# LAMEBOY.net
KiCad netlist of a schematic drawn in EAGLE
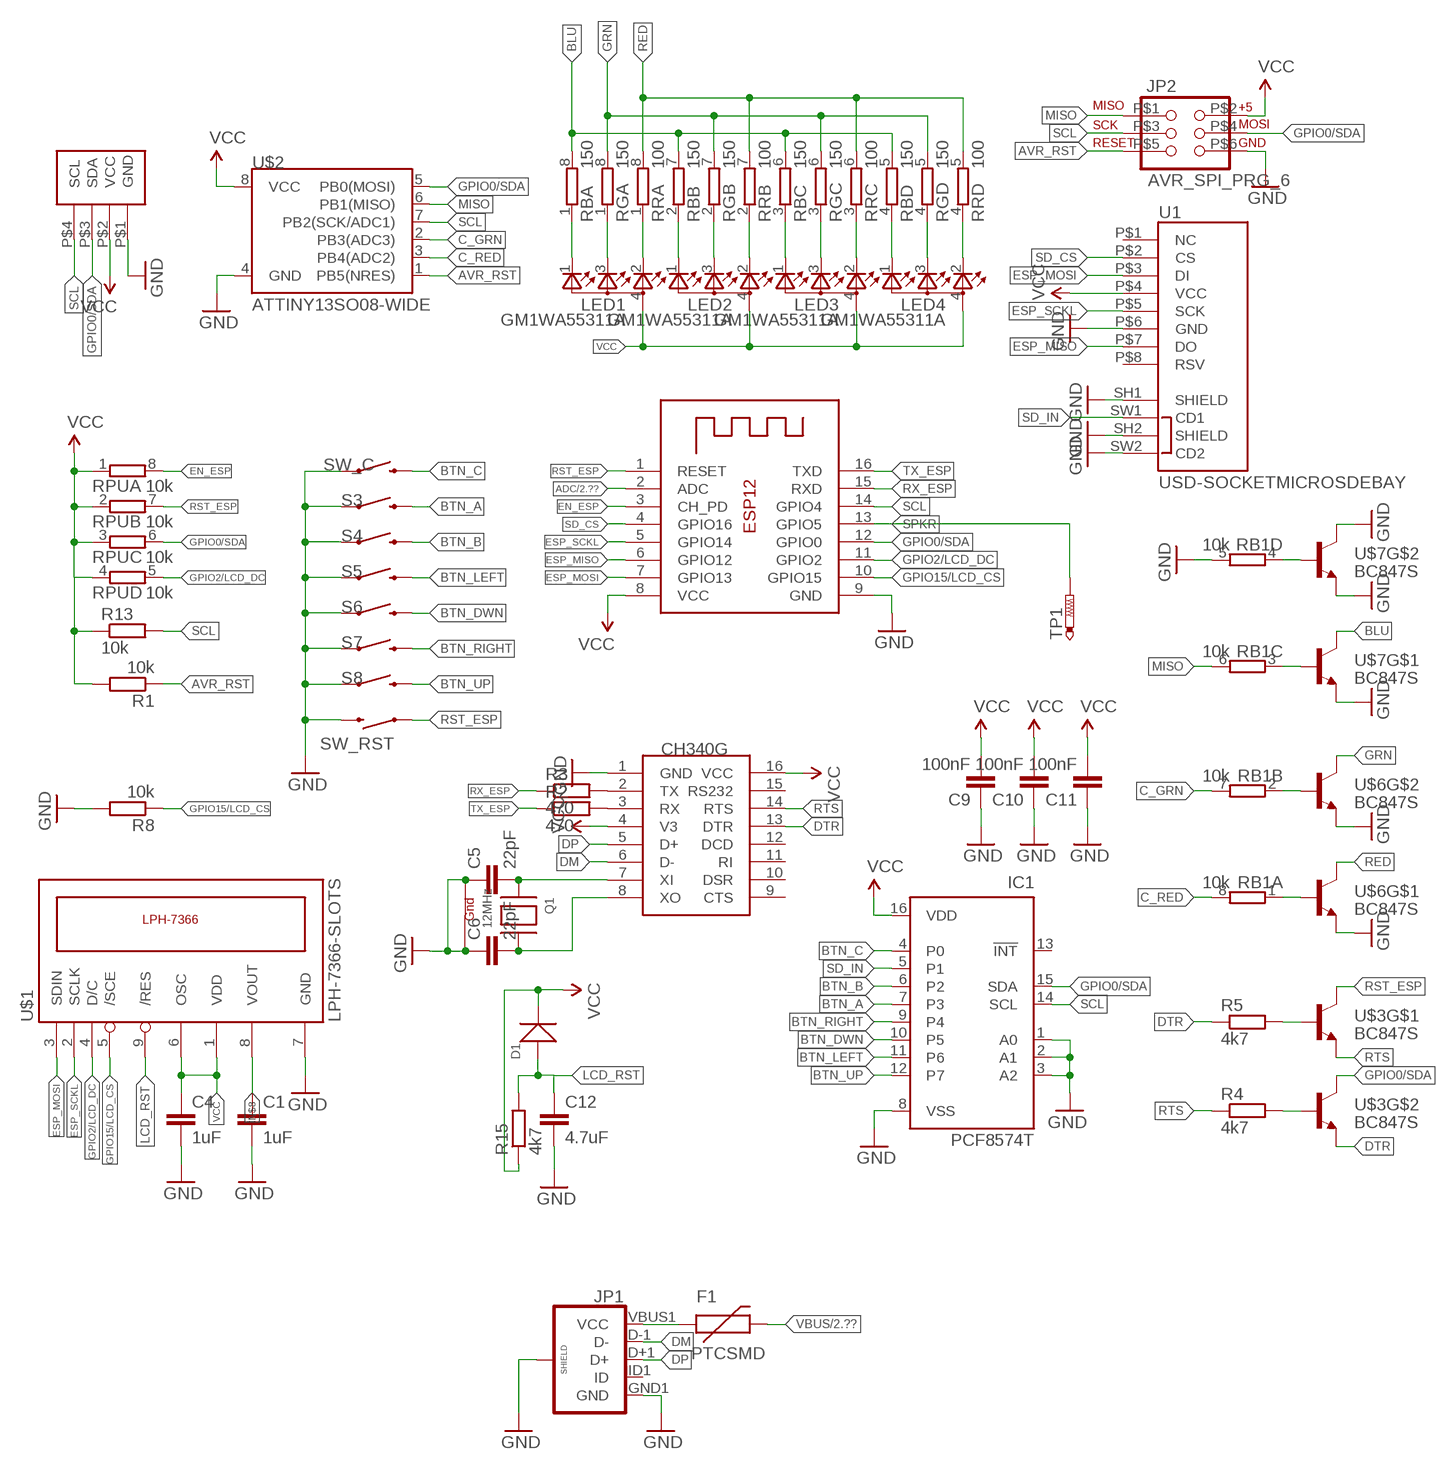
[diagram p0: schematic, sheet 1]
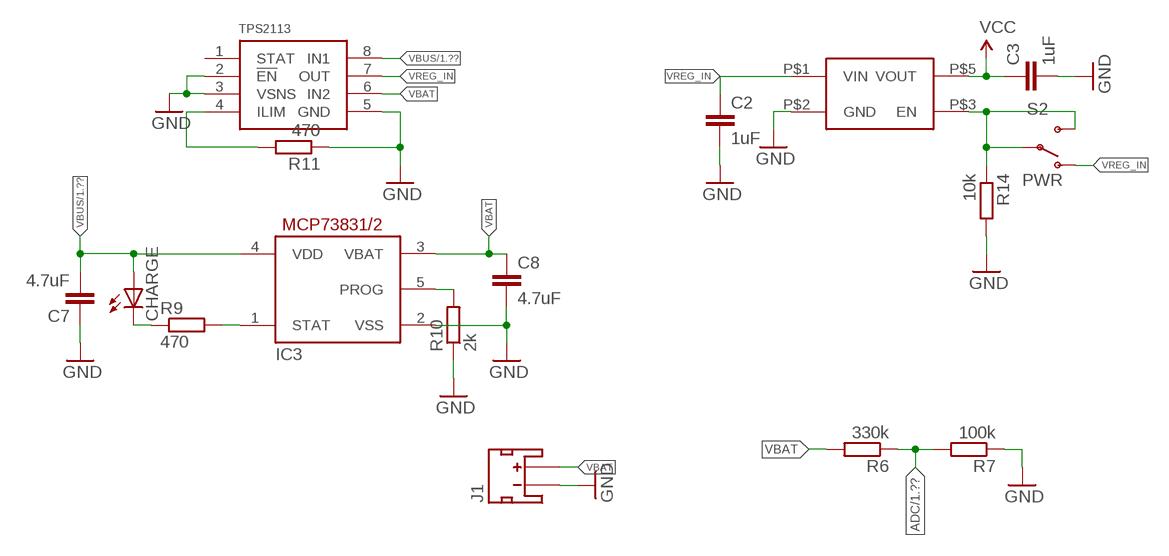
[diagram p1: schematic, sheet 2]

(export (version "E")
  (design (tool "Eeschema 10.0.6"))
  (components
    (comp (ref "C1")
      (value "1uF")
      (footprint "eagle-import:C0805")
      (libsource (lib "eagle-import") (part "C-EUC0805"))
    )
    (comp (ref "C4")
      (value "1uF")
      (footprint "eagle-import:C0805")
      (libsource (lib "eagle-import") (part "C-EUC0805"))
    )
    (comp (ref "C5")
      (value "22pF")
      (footprint "eagle-import:C0805")
      (libsource (lib "eagle-import") (part "C-EUC0805"))
    )
    (comp (ref "C6")
      (value "22pF")
      (footprint "eagle-import:C0805")
      (libsource (lib "eagle-import") (part "C-EUC0805"))
    )
    (comp (ref "C9")
      (value "100nF")
      (footprint "eagle-import:C0805")
      (libsource (lib "eagle-import") (part "C-EUC0805"))
    )
    (comp (ref "C10")
      (value "100nF")
      (footprint "eagle-import:C0805")
      (libsource (lib "eagle-import") (part "C-EUC0805"))
    )
    (comp (ref "C11")
      (value "100nF")
      (footprint "eagle-import:C0805")
      (libsource (lib "eagle-import") (part "C-EUC0805"))
    )
    (comp (ref "C12")
      (value "4.7uF")
      (footprint "eagle-import:C0805")
      (libsource (lib "eagle-import") (part "C-EUC0805"))
    )
    (comp (ref "CH340G")
      (value "CH340GCH340G")
      (footprint "eagle-import:SOIC16")
      (libsource (lib "eagle-import") (part "CH340GCH340G"))
    )
    (comp (ref "D1")
      (value "DIODE'1N4148-SMD'")
      (footprint "eagle-import:LL-34")
      (libsource (lib "eagle-import") (part "DIODE'1N4148-SMD'"))
    )
    (comp (ref "F1")
      (value "PTCSMD")
      (footprint "eagle-import:PTC-1206")
      (libsource (lib "eagle-import") (part "PTCSMD"))
    )
    (comp (ref "IC1")
      (value "PCF8574T")
      (footprint "eagle-import:SO16W")
      (fields (field (name "MPN") "PCF8574T/3,512"))
      (libsource (lib "eagle-import") (part "PCF8574T"))
    )
    (comp (ref "JP1")
      (value "USB_MICROB_PLUG-IDK")
      (footprint "eagle-import:USB-AB-MICRO-SMD_SLOT")
      (libsource (lib "eagle-import") (part "USB_MICROB_PLUG-IDK"))
    )
    (comp (ref "JP2")
      (value "AVR_SPI_PRG_6")
      (footprint "eagle-import:2X3_SMD_PAD")
      (libsource (lib "eagle-import") (part "AVR_SPI_PRG_6"))
    )
    (comp (ref "LED1")
      (value "GM1WA55311A")
      (footprint "eagle-import:GM1WA55311A")
      (libsource (lib "eagle-import") (part "GM1WA55311A"))
    )
    (comp (ref "LED2")
      (value "GM1WA55311A")
      (footprint "eagle-import:GM1WA55311A")
      (libsource (lib "eagle-import") (part "GM1WA55311A"))
    )
    (comp (ref "LED3")
      (value "GM1WA55311A")
      (footprint "eagle-import:GM1WA55311A")
      (libsource (lib "eagle-import") (part "GM1WA55311A"))
    )
    (comp (ref "LED4")
      (value "GM1WA55311A")
      (footprint "eagle-import:GM1WA55311A")
      (libsource (lib "eagle-import") (part "GM1WA55311A"))
    )
    (comp (ref "Q1")
      (value "12MHz")
      (footprint "eagle-import:NX3225_BIGGER")
      (libsource (lib "eagle-import") (part "XTAL-4BIGGER"))
    )
    (comp (ref "R1")
      (value "10k")
      (footprint "eagle-import:R0805")
      (libsource (lib "eagle-import") (part "R-EU_R0805"))
    )
    (comp (ref "R2")
      (value "470")
      (footprint "eagle-import:R0805")
      (libsource (lib "eagle-import") (part "R-EU_R0805"))
    )
    (comp (ref "R3")
      (value "470")
      (footprint "eagle-import:R0805")
      (libsource (lib "eagle-import") (part "R-EU_R0805"))
    )
    (comp (ref "R4")
      (value "4k7")
      (footprint "eagle-import:R0805")
      (libsource (lib "eagle-import") (part "R-EU_R0805"))
    )
    (comp (ref "R5")
      (value "4k7")
      (footprint "eagle-import:R0805")
      (libsource (lib "eagle-import") (part "R-EU_R0805"))
    )
    (comp (ref "R8")
      (value "10k")
      (footprint "eagle-import:R0805")
      (libsource (lib "eagle-import") (part "R-EU_R0805"))
    )
    (comp (ref "R13")
      (value "10k")
      (footprint "eagle-import:R0805")
      (libsource (lib "eagle-import") (part "R-EU_R0805"))
    )
    (comp (ref "R15")
      (value "4k7")
      (footprint "eagle-import:R0805")
      (libsource (lib "eagle-import") (part "R-EU_R0805"))
    )
    (comp (ref "RB")
      (value "150")
      (footprint "eagle-import:0603-ARC")
      (libsource (lib "eagle-import") (part "4R-N0603-ARC"))
    )
    (comp (ref "RB1")
      (value "10k")
      (footprint "eagle-import:0603-ARC")
      (libsource (lib "eagle-import") (part "4R-N0603-ARC"))
    )
    (comp (ref "RG")
      (value "150")
      (footprint "eagle-import:0603-ARC")
      (libsource (lib "eagle-import") (part "4R-N0603-ARC"))
    )
    (comp (ref "RPU")
      (value "10k")
      (footprint "eagle-import:0603-ARC")
      (libsource (lib "eagle-import") (part "4R-N0603-ARC"))
    )
    (comp (ref "RR")
      (value "100")
      (footprint "eagle-import:0603-ARC")
      (libsource (lib "eagle-import") (part "4R-N0603-ARC"))
    )
    (comp (ref "S3")
      (value "SWITCH-MOMENTARY-2SMD-4")
      (footprint "eagle-import:TACTILE_SWITCH_TALL")
      (libsource (lib "eagle-import") (part "SWITCH-MOMENTARY-2SMD-4"))
    )
    (comp (ref "S4")
      (value "SWITCH-MOMENTARY-2SMD-4")
      (footprint "eagle-import:TACTILE_SWITCH_TALL")
      (libsource (lib "eagle-import") (part "SWITCH-MOMENTARY-2SMD-4"))
    )
    (comp (ref "S5")
      (value "SWITCH-MOMENTARY-2SMD-4")
      (footprint "eagle-import:TACTILE_SWITCH_TALL")
      (libsource (lib "eagle-import") (part "SWITCH-MOMENTARY-2SMD-4"))
    )
    (comp (ref "S6")
      (value "SWITCH-MOMENTARY-2SMD-4")
      (footprint "eagle-import:TACTILE_SWITCH_TALL")
      (libsource (lib "eagle-import") (part "SWITCH-MOMENTARY-2SMD-4"))
    )
    (comp (ref "S7")
      (value "SWITCH-MOMENTARY-2SMD-4")
      (footprint "eagle-import:TACTILE_SWITCH_TALL")
      (libsource (lib "eagle-import") (part "SWITCH-MOMENTARY-2SMD-4"))
    )
    (comp (ref "S8")
      (value "SWITCH-MOMENTARY-2SMD-4")
      (footprint "eagle-import:TACTILE_SWITCH_TALL")
      (libsource (lib "eagle-import") (part "SWITCH-MOMENTARY-2SMD-4"))
    )
    (comp (ref "SW_C")
      (value "SWITCH-MOMENTARY-2-SMD-1101NE")
      (footprint "eagle-import:TACTILE-SWITCH-1101NE")
      (libsource (lib "eagle-import") (part "SWITCH-MOMENTARY-2-SMD-1101NE"))
    )
    (comp (ref "SW_RST")
      (value "SWITCH-MOMENTARY-2-SMD-1101NE")
      (footprint "eagle-import:TACTILE-SWITCH-1101NE")
      (libsource (lib "eagle-import") (part "SWITCH-MOMENTARY-2-SMD-1101NE"))
    )
    (comp (ref "TP1")
      (value "PTR1B1,27")
      (footprint "eagle-import:B1,27")
      (libsource (lib "eagle-import") (part "PTR1B1,27"))
    )
    (comp (ref "U$1")
      (value "LPH-7366-SLOTS")
      (footprint "eagle-import:LPH-7366-SLOTS")
      (libsource (lib "eagle-import") (part "LPH-7366-SLOTS"))
    )
    (comp (ref "U$2")
      (value "ATTINY13SO08-WIDE")
      (footprint "eagle-import:SO08-EIAJ")
      (libsource (lib "eagle-import") (part "ATTINY13SO08-WIDE"))
    )
    (comp (ref "U$3")
      (value "BC847S")
      (footprint "eagle-import:SOT363")
      (libsource (lib "eagle-import") (part "MMDT3904"))
    )
    (comp (ref "U$6")
      (value "BC847S")
      (footprint "eagle-import:SOT363")
      (libsource (lib "eagle-import") (part "MMDT3904"))
    )
    (comp (ref "U$7")
      (value "BC847S")
      (footprint "eagle-import:SOT363")
      (libsource (lib "eagle-import") (part "MMDT3904"))
    )
    (comp (ref "U$10")
      (value "I2C_GROVE")
      (footprint "eagle-import:I2C_GROVE")
      (libsource (lib "eagle-import") (part "I2C_GROVE"))
    )
    (comp (ref "U1")
      (value "USD-SOCKETMICROSDEBAY")
      (footprint "eagle-import:MICRO-SD-SOCKET-EBAY")
      (libsource (lib "eagle-import") (part "USD-SOCKETMICROSDEBAY"))
    )
    (comp (ref "X1")
      (value "ESP-12")
      (footprint "eagle-import:ESP-12")
      (libsource (lib "eagle-import") (part "ESP-12"))
    )
    (comp (ref "C2")
      (value "1uF")
      (footprint "eagle-import:C0805")
      (libsource (lib "eagle-import") (part "C-EUC0805"))
    )
    (comp (ref "C3")
      (value "1uF")
      (footprint "eagle-import:C0805")
      (libsource (lib "eagle-import") (part "C-EUC0805"))
    )
    (comp (ref "C7")
      (value "4.7uF")
      (footprint "eagle-import:C0805")
      (libsource (lib "eagle-import") (part "C-EUC0805"))
    )
    (comp (ref "C8")
      (value "4.7uF")
      (footprint "eagle-import:C0805")
      (libsource (lib "eagle-import") (part "C-EUC0805"))
    )
    (comp (ref "CHARGE")
      (value "LEDCHARLIE")
      (footprint "eagle-import:CHIPLED_0603_CHARLIE")
      (libsource (lib "eagle-import") (part "LEDCHARLIE"))
    )
    (comp (ref "IC3")
      (value "MCP73831")
      (footprint "eagle-import:SOT23-5L")
      (libsource (lib "eagle-import") (part "MCP73831/OT"))
    )
    (comp (ref "J1")
      (value "JST_2MM_MALE")
      (footprint "eagle-import:JST-2-SMD")
      (libsource (lib "eagle-import") (part "JST_2MM_MALE"))
    )
    (comp (ref "R6")
      (value "330k")
      (footprint "eagle-import:R0805")
      (libsource (lib "eagle-import") (part "R-EU_R0805"))
    )
    (comp (ref "R7")
      (value "100k")
      (footprint "eagle-import:R0805")
      (libsource (lib "eagle-import") (part "R-EU_R0805"))
    )
    (comp (ref "R9")
      (value "470")
      (footprint "eagle-import:R0805")
      (libsource (lib "eagle-import") (part "R-EU_R0805"))
    )
    (comp (ref "R10")
      (value "2k")
      (footprint "eagle-import:R0805")
      (libsource (lib "eagle-import") (part "R-EU_R0805"))
    )
    (comp (ref "R11")
      (value "470")
      (footprint "eagle-import:R0805")
      (libsource (lib "eagle-import") (part "R-EU_R0805"))
    )
    (comp (ref "R14")
      (value "10k")
      (footprint "eagle-import:R0805")
      (libsource (lib "eagle-import") (part "R-EU_R0805"))
    )
    (comp (ref "S2")
      (value "PWR")
      (footprint "eagle-import:SWITCH-SPST-SMD-A")
      (libsource (lib "eagle-import") (part "SWITCH-SPDT-SMD-A"))
    )
    (comp (ref "U$4")
      (value "TPS2113-PW")
      (footprint "eagle-import:TEXAS-PW")
      (libsource (lib "eagle-import") (part "TPS2113-PW"))
    )
    (comp (ref "U$9")
      (value "AP2112KAP2112K")
      (footprint "eagle-import:AP2112")
      (libsource (lib "eagle-import") (part "AP2112KAP2112K"))
    )
  )
  (nets
    (net (code "1") (name "ADC") (class "Default")
      (node (ref "R6") (pin "1") (pinfunction "1_1") (pintype "passive"))
      (node (ref "R7") (pin "2") (pinfunction "2_2") (pintype "passive"))
      (node (ref "X1") (pin "2") (pinfunction "ADC_2") (pintype "passive"))
    )
    (net (code "2") (name "AVR_RST") (class "Default")
      (node (ref "JP2") (pin "P$5") (pinfunction "5_P$5") (pintype "passive"))
      (node (ref "R1") (pin "1") (pinfunction "1_1") (pintype "passive"))
      (node (ref "U$2") (pin "1") (pinfunction "PB5(NRES)_1") (pintype "bidirectional"))
    )
    (net (code "3") (name "BLU") (class "Default")
      (node (ref "RB") (pin "5") (pinfunction "2_5") (pintype "passive"))
      (node (ref "RB") (pin "6") (pinfunction "2_6") (pintype "passive"))
      (node (ref "RB") (pin "7") (pinfunction "2_7") (pintype "passive"))
      (node (ref "RB") (pin "8") (pinfunction "2_8") (pintype "passive"))
      (node (ref "U$7") (pin "3") (pinfunction "C_3") (pintype "passive"))
    )
    (net (code "4") (name "BTN_A") (class "Default")
      (node (ref "IC1") (pin "7") (pinfunction "P3_7") (pintype "bidirectional"))
      (node (ref "S3") (pin "B2") (pinfunction "2_B2") (pintype "passive"))
    )
    (net (code "5") (name "BTN_B") (class "Default")
      (node (ref "IC1") (pin "6") (pinfunction "P2_6") (pintype "bidirectional"))
      (node (ref "S4") (pin "B2") (pinfunction "2_B2") (pintype "passive"))
    )
    (net (code "6") (name "BTN_C") (class "Default")
      (node (ref "IC1") (pin "4") (pinfunction "P0_4") (pintype "bidirectional"))
      (node (ref "SW_C") (pin "P$2") (pinfunction "2_P$2") (pintype "passive"))
    )
    (net (code "7") (name "BTN_DWN") (class "Default")
      (node (ref "IC1") (pin "10") (pinfunction "P5_10") (pintype "bidirectional"))
      (node (ref "S6") (pin "B2") (pinfunction "2_B2") (pintype "passive"))
    )
    (net (code "8") (name "BTN_LEFT") (class "Default")
      (node (ref "IC1") (pin "11") (pinfunction "P6_11") (pintype "bidirectional"))
      (node (ref "S5") (pin "B2") (pinfunction "2_B2") (pintype "passive"))
    )
    (net (code "9") (name "BTN_RIGHT") (class "Default")
      (node (ref "IC1") (pin "9") (pinfunction "P4_9") (pintype "bidirectional"))
      (node (ref "S7") (pin "B2") (pinfunction "2_B2") (pintype "passive"))
    )
    (net (code "10") (name "BTN_UP") (class "Default")
      (node (ref "IC1") (pin "12") (pinfunction "P7_12") (pintype "bidirectional"))
      (node (ref "S8") (pin "B2") (pinfunction "2_B2") (pintype "passive"))
    )
    (net (code "11") (name "C_GRN") (class "Default")
      (node (ref "RB1") (pin "7") (pinfunction "2_7") (pintype "passive"))
      (node (ref "U$2") (pin "2") (pinfunction "PB3(ADC3)_2") (pintype "bidirectional"))
    )
    (net (code "12") (name "C_RED") (class "Default")
      (node (ref "RB1") (pin "8") (pinfunction "2_8") (pintype "passive"))
      (node (ref "U$2") (pin "3") (pinfunction "PB4(ADC2)_3") (pintype "bidirectional"))
    )
    (net (code "13") (name "DM") (class "Default")
      (node (ref "CH340G") (pin "6") (pinfunction "D-_6") (pintype "bidirectional"))
      (node (ref "JP1") (pin "D-1") (pinfunction "D-_D-1") (pintype "bidirectional"))
    )
    (net (code "14") (name "DP") (class "Default")
      (node (ref "CH340G") (pin "5") (pinfunction "D+_5") (pintype "bidirectional"))
      (node (ref "JP1") (pin "D+1") (pinfunction "D+_D+1") (pintype "bidirectional"))
    )
    (net (code "15") (name "DTR") (class "Default")
      (node (ref "CH340G") (pin "13") (pinfunction "DTR_13") (pintype "bidirectional"))
      (node (ref "R5") (pin "1") (pinfunction "1_1") (pintype "passive"))
      (node (ref "U$3") (pin "1") (pinfunction "E_1") (pintype "passive"))
    )
    (net (code "16") (name "EN_ESP") (class "Default")
      (node (ref "RPU") (pin "8") (pinfunction "2_8") (pintype "passive"))
      (node (ref "X1") (pin "3") (pinfunction "CH_PD_3") (pintype "input"))
    )
    (net (code "17") (name "ESP_MISO") (class "Default")
      (node (ref "U1") (pin "P$7") (pinfunction "DO_P$7") (pintype "bidirectional"))
      (node (ref "X1") (pin "6") (pinfunction "GPIO12_6") (pintype "bidirectional"))
    )
    (net (code "18") (name "ESP_MOSI") (class "Default")
      (node (ref "U$1") (pin "3") (pinfunction "SDIN_3") (pintype "input"))
      (node (ref "U1") (pin "P$3") (pinfunction "DI_P$3") (pintype "bidirectional"))
      (node (ref "X1") (pin "7") (pinfunction "GPIO13_7") (pintype "bidirectional"))
    )
    (net (code "19") (name "ESP_SCKL") (class "Default")
      (node (ref "U$1") (pin "2") (pinfunction "SCLK_2") (pintype "input"))
      (node (ref "U1") (pin "P$5") (pinfunction "SCK_P$5") (pintype "bidirectional"))
      (node (ref "X1") (pin "5") (pinfunction "GPIO14_5") (pintype "bidirectional"))
    )
    (net (code "20") (name "GND") (class "Default")
      (node (ref "C1") (pin "2") (pinfunction "2_2") (pintype "passive"))
      (node (ref "C10") (pin "1") (pinfunction "1_1") (pintype "passive"))
      (node (ref "C11") (pin "1") (pinfunction "1_1") (pintype "passive"))
      (node (ref "C12") (pin "2") (pinfunction "2_2") (pintype "passive"))
      (node (ref "C2") (pin "2") (pinfunction "2_2") (pintype "passive"))
      (node (ref "C3") (pin "2") (pinfunction "2_2") (pintype "passive"))
      (node (ref "C4") (pin "2") (pinfunction "2_2") (pintype "passive"))
      (node (ref "C5") (pin "1") (pinfunction "1_1") (pintype "passive"))
      (node (ref "C6") (pin "1") (pinfunction "1_1") (pintype "passive"))
      (node (ref "C7") (pin "1") (pinfunction "1_1") (pintype "passive"))
      (node (ref "C8") (pin "2") (pinfunction "2_2") (pintype "passive"))
      (node (ref "C9") (pin "1") (pinfunction "1_1") (pintype "passive"))
      (node (ref "CH340G") (pin "1") (pinfunction "GND_1") (pintype "bidirectional"))
      (node (ref "IC1") (pin "1") (pinfunction "A0_1") (pintype "input"))
      (node (ref "IC1") (pin "2") (pinfunction "A1_2") (pintype "input"))
      (node (ref "IC1") (pin "3") (pinfunction "A2_3") (pintype "input"))
      (node (ref "IC1") (pin "8") (pinfunction "VSS_8") (pintype "power_in"))
      (node (ref "IC3") (pin "2") (pinfunction "VSS_2") (pintype "power_in"))
      (node (ref "J1") (pin "1") (pinfunction "-_1") (pintype "bidirectional"))
      (node (ref "JP1") (pin "GND1") (pinfunction "GND_GND1") (pintype "bidirectional"))
      (node (ref "JP1") (pin "P$1") (pinfunction "SHIELD_P$1") (pintype "bidirectional"))
      (node (ref "JP1") (pin "P$2") (pinfunction "SHIELD_P$2") (pintype "bidirectional"))
      (node (ref "JP1") (pin "P$3") (pinfunction "SHIELD_P$3") (pintype "bidirectional"))
      (node (ref "JP1") (pin "P$4") (pinfunction "SHIELD_P$4") (pintype "bidirectional"))
      (node (ref "JP2") (pin "P$6") (pinfunction "6_P$6") (pintype "passive"))
      (node (ref "Q1") (pin "2") (pinfunction "G2_2") (pintype "power_in"))
      (node (ref "Q1") (pin "4") (pinfunction "G1_4") (pintype "power_in"))
      (node (ref "R10") (pin "1") (pinfunction "1_1") (pintype "passive"))
      (node (ref "R11") (pin "1") (pinfunction "1_1") (pintype "passive"))
      (node (ref "R14") (pin "2") (pinfunction "2_2") (pintype "passive"))
      (node (ref "R7") (pin "1") (pinfunction "1_1") (pintype "passive"))
      (node (ref "R8") (pin "2") (pinfunction "2_2") (pintype "passive"))
      (node (ref "RB1") (pin "5") (pinfunction "2_5") (pintype "passive"))
      (node (ref "S3") (pin "A2") (pinfunction "1_A2") (pintype "passive"))
      (node (ref "S4") (pin "A2") (pinfunction "1_A2") (pintype "passive"))
      (node (ref "S5") (pin "A2") (pinfunction "1_A2") (pintype "passive"))
      (node (ref "S6") (pin "A2") (pinfunction "1_A2") (pintype "passive"))
      (node (ref "S7") (pin "A2") (pinfunction "1_A2") (pintype "passive"))
      (node (ref "S8") (pin "A2") (pinfunction "1_A2") (pintype "passive"))
      (node (ref "SW_C") (pin "P$1") (pinfunction "1_P$1") (pintype "passive"))
      (node (ref "SW_RST") (pin "P$2") (pinfunction "2_P$2") (pintype "passive"))
      (node (ref "U$1") (pin "7") (pinfunction "GND_7") (pintype "power_in"))
      (node (ref "U$10") (pin "P$1") (pinfunction "GND_P$1") (pintype "bidirectional"))
      (node (ref "U$2") (pin "4") (pinfunction "GND_4") (pintype "bidirectional"))
      (node (ref "U$4") (pin "2") (pinfunction "~{EN}_2") (pintype "bidirectional"))
      (node (ref "U$4") (pin "3") (pinfunction "VSNS_3") (pintype "bidirectional"))
      (node (ref "U$4") (pin "5") (pinfunction "GND_5") (pintype "bidirectional"))
      (node (ref "U$6") (pin "1") (pinfunction "E_1") (pintype "passive"))
      (node (ref "U$6") (pin "4") (pinfunction "E_4") (pintype "passive"))
      (node (ref "U$7") (pin "1") (pinfunction "E_1") (pintype "passive"))
      (node (ref "U$7") (pin "4") (pinfunction "E_4") (pintype "passive"))
      (node (ref "U$7") (pin "6") (pinfunction "C_6") (pintype "passive"))
      (node (ref "U$9") (pin "P$2") (pinfunction "GND_P$2") (pintype "bidirectional"))
      (node (ref "U1") (pin "P$6") (pinfunction "GND_P$6") (pintype "bidirectional"))
      (node (ref "U1") (pin "SH1") (pinfunction "SHIELD_SH1") (pintype "bidirectional"))
      (node (ref "U1") (pin "SH2") (pinfunction "SHIELD_SH2") (pintype "bidirectional"))
      (node (ref "U1") (pin "SW2") (pinfunction "CD2_SW2") (pintype "bidirectional"))
      (node (ref "X1") (pin "9") (pinfunction "GND_9") (pintype "power_in"))
    )
    (net (code "21") (name "GPIO0{slash}SDA") (class "Default")
      (node (ref "IC1") (pin "15") (pinfunction "SDA_15") (pintype "bidirectional"))
      (node (ref "JP2") (pin "P$4") (pinfunction "4_P$4") (pintype "passive"))
      (node (ref "RPU") (pin "6") (pinfunction "2_6") (pintype "passive"))
      (node (ref "U$10") (pin "P$3") (pinfunction "SDA_P$3") (pintype "bidirectional"))
      (node (ref "U$2") (pin "5") (pinfunction "PB0(MOSI)_5") (pintype "bidirectional"))
      (node (ref "U$3") (pin "6") (pinfunction "C_6") (pintype "passive"))
      (node (ref "X1") (pin "12") (pinfunction "GPIO0_12") (pintype "bidirectional"))
    )
    (net (code "22") (name "GPIO2{slash}LCD_DC") (class "Default")
      (node (ref "RPU") (pin "5") (pinfunction "2_5") (pintype "passive"))
      (node (ref "U$1") (pin "4") (pinfunction "D/C_4") (pintype "input"))
      (node (ref "X1") (pin "11") (pinfunction "GPIO2_11") (pintype "bidirectional"))
    )
    (net (code "23") (name "GPIO15{slash}LCD_CS") (class "Default")
      (node (ref "R8") (pin "1") (pinfunction "1_1") (pintype "passive"))
      (node (ref "U$1") (pin "5") (pinfunction "/SCE_5") (pintype "input"))
      (node (ref "X1") (pin "10") (pinfunction "GPIO15_10") (pintype "bidirectional"))
    )
    (net (code "24") (name "GRN") (class "Default")
      (node (ref "RG") (pin "5") (pinfunction "2_5") (pintype "passive"))
      (node (ref "RG") (pin "6") (pinfunction "2_6") (pintype "passive"))
      (node (ref "RG") (pin "7") (pinfunction "2_7") (pintype "passive"))
      (node (ref "RG") (pin "8") (pinfunction "2_8") (pintype "passive"))
      (node (ref "U$6") (pin "6") (pinfunction "C_6") (pintype "passive"))
    )
    (net (code "25") (name "LCD_RST") (class "Default")
      (node (ref "C12") (pin "1") (pinfunction "1_1") (pintype "passive"))
      (node (ref "D1") (pin "A") (pinfunction "+_A") (pintype "passive"))
      (node (ref "R15") (pin "2") (pinfunction "2_2") (pintype "passive"))
      (node (ref "U$1") (pin "9") (pinfunction "/RES_9") (pintype "input"))
    )
    (net (code "26") (name "MISO") (class "Default")
      (node (ref "JP2") (pin "P$1") (pinfunction "1_P$1") (pintype "passive"))
      (node (ref "RB1") (pin "6") (pinfunction "2_6") (pintype "passive"))
      (node (ref "U$2") (pin "6") (pinfunction "PB1(MISO)_6") (pintype "bidirectional"))
    )
    (net (code "27") (name "N$8") (class "Default")
      (node (ref "C1") (pin "1") (pinfunction "1_1") (pintype "passive"))
      (node (ref "U$1") (pin "8") (pinfunction "VOUT_8") (pintype "passive"))
    )
    (net (code "28") (name "Net-(CH340G-RX)") (class "Default")
      (node (ref "CH340G") (pin "3") (pinfunction "RX_3") (pintype "bidirectional"))
      (node (ref "R2") (pin "2") (pinfunction "2_2") (pintype "passive"))
    )
    (net (code "29") (name "Net-(CH340G-TX)") (class "Default")
      (node (ref "CH340G") (pin "2") (pinfunction "TX_2") (pintype "bidirectional"))
      (node (ref "R3") (pin "2") (pinfunction "2_2") (pintype "passive"))
    )
    (net (code "30") (name "Net-(CH340G-XI)") (class "Default")
      (node (ref "C5") (pin "2") (pinfunction "2_2") (pintype "passive"))
      (node (ref "CH340G") (pin "7") (pinfunction "XI_7") (pintype "bidirectional"))
      (node (ref "Q1") (pin "1") (pinfunction "X1_1") (pintype "bidirectional"))
    )
    (net (code "31") (name "Net-(CH340G-XO)") (class "Default")
      (node (ref "C6") (pin "2") (pinfunction "2_2") (pintype "passive"))
      (node (ref "CH340G") (pin "8") (pinfunction "XO_8") (pintype "bidirectional"))
      (node (ref "Q1") (pin "3") (pinfunction "X2_3") (pintype "bidirectional"))
    )
    (net (code "32") (name "Net-(CHARGE-PadC)") (class "Default")
      (node (ref "CHARGE") (pin "C") (pinfunction "C_C") (pintype "passive"))
      (node (ref "R9") (pin "1") (pinfunction "1_1") (pintype "passive"))
    )
    (net (code "33") (name "Net-(IC3-PROG)") (class "Default")
      (node (ref "IC3") (pin "5") (pinfunction "PROG_5") (pintype "input"))
      (node (ref "R10") (pin "2") (pinfunction "2_2") (pintype "passive"))
    )
    (net (code "34") (name "Net-(IC3-STAT)") (class "Default")
      (node (ref "IC3") (pin "1") (pinfunction "STAT_1") (pintype "output"))
      (node (ref "R9") (pin "2") (pinfunction "2_2") (pintype "passive"))
    )
    (net (code "35") (name "Net-(JP1-VCC)") (class "Default")
      (node (ref "F1") (pin "1") (pinfunction "1_1") (pintype "bidirectional"))
      (node (ref "JP1") (pin "VBUS1") (pinfunction "VCC_VBUS1") (pintype "bidirectional"))
    )
    (net (code "36") (name "Net-(LED1-CBLUE)") (class "Default")
      (node (ref "LED1") (pin "3") (pinfunction "CBLUE_3") (pintype "passive"))
      (node (ref "RG") (pin "1") (pinfunction "1_1") (pintype "passive"))
    )
    (net (code "37") (name "Net-(LED1-CGREEN)") (class "Default")
      (node (ref "LED1") (pin "1") (pinfunction "CGREEN_1") (pintype "passive"))
      (node (ref "RB") (pin "1") (pinfunction "1_1") (pintype "passive"))
    )
    (net (code "38") (name "Net-(LED1-CRED)") (class "Default")
      (node (ref "LED1") (pin "2") (pinfunction "CRED_2") (pintype "passive"))
      (node (ref "RR") (pin "1") (pinfunction "1_1") (pintype "passive"))
    )
    (net (code "39") (name "Net-(LED2-CBLUE)") (class "Default")
      (node (ref "LED2") (pin "3") (pinfunction "CBLUE_3") (pintype "passive"))
      (node (ref "RG") (pin "2") (pinfunction "1_2") (pintype "passive"))
    )
    (net (code "40") (name "Net-(LED2-CGREEN)") (class "Default")
      (node (ref "LED2") (pin "1") (pinfunction "CGREEN_1") (pintype "passive"))
      (node (ref "RB") (pin "2") (pinfunction "1_2") (pintype "passive"))
    )
    (net (code "41") (name "Net-(LED2-CRED)") (class "Default")
      (node (ref "LED2") (pin "2") (pinfunction "CRED_2") (pintype "passive"))
      (node (ref "RR") (pin "2") (pinfunction "1_2") (pintype "passive"))
    )
    (net (code "42") (name "Net-(LED3-CBLUE)") (class "Default")
      (node (ref "LED3") (pin "3") (pinfunction "CBLUE_3") (pintype "passive"))
      (node (ref "RG") (pin "3") (pinfunction "1_3") (pintype "passive"))
    )
    (net (code "43") (name "Net-(LED3-CGREEN)") (class "Default")
      (node (ref "LED3") (pin "1") (pinfunction "CGREEN_1") (pintype "passive"))
      (node (ref "RB") (pin "3") (pinfunction "1_3") (pintype "passive"))
    )
    (net (code "44") (name "Net-(LED3-CRED)") (class "Default")
      (node (ref "LED3") (pin "2") (pinfunction "CRED_2") (pintype "passive"))
      (node (ref "RR") (pin "3") (pinfunction "1_3") (pintype "passive"))
    )
    (net (code "45") (name "Net-(LED4-CBLUE)") (class "Default")
      (node (ref "LED4") (pin "3") (pinfunction "CBLUE_3") (pintype "passive"))
      (node (ref "RG") (pin "4") (pinfunction "1_4") (pintype "passive"))
    )
    (net (code "46") (name "Net-(LED4-CGREEN)") (class "Default")
      (node (ref "LED4") (pin "1") (pinfunction "CGREEN_1") (pintype "passive"))
      (node (ref "RB") (pin "4") (pinfunction "1_4") (pintype "passive"))
    )
    (net (code "47") (name "Net-(LED4-CRED)") (class "Default")
      (node (ref "LED4") (pin "2") (pinfunction "CRED_2") (pintype "passive"))
      (node (ref "RR") (pin "4") (pinfunction "1_4") (pintype "passive"))
    )
    (net (code "48") (name "Net-(RB1B-1)") (class "Default")
      (node (ref "RB1") (pin "2") (pinfunction "1_2") (pintype "passive"))
      (node (ref "U$6") (pin "2") (pinfunction "B_2") (pintype "passive"))
    )
    (net (code "49") (name "Net-(RB1C-1)") (class "Default")
      (node (ref "RB1") (pin "3") (pinfunction "1_3") (pintype "passive"))
      (node (ref "U$7") (pin "5") (pinfunction "B_5") (pintype "passive"))
    )
    (net (code "50") (name "Net-(RB1D-1)") (class "Default")
      (node (ref "RB1") (pin "4") (pinfunction "1_4") (pintype "passive"))
      (node (ref "U$7") (pin "2") (pinfunction "B_2") (pintype "passive"))
    )
    (net (code "51") (name "Net-(S2-P)") (class "Default")
      (node (ref "R14") (pin "1") (pinfunction "1_1") (pintype "passive"))
      (node (ref "S2") (pin "2") (pinfunction "P_2") (pintype "passive"))
      (node (ref "S2") (pin "3") (pinfunction "S_3") (pintype "passive"))
      (node (ref "U$9") (pin "P$3") (pinfunction "EN_P$3") (pintype "bidirectional"))
    )
    (net (code "52") (name "Net-(U$3A-B)") (class "Default")
      (node (ref "R5") (pin "2") (pinfunction "2_2") (pintype "passive"))
      (node (ref "U$3") (pin "5") (pinfunction "B_5") (pintype "passive"))
    )
    (net (code "53") (name "Net-(U$3B-B)") (class "Default")
      (node (ref "R4") (pin "2") (pinfunction "2_2") (pintype "passive"))
      (node (ref "U$3") (pin "2") (pinfunction "B_2") (pintype "passive"))
    )
    (net (code "54") (name "Net-(U$4-ILIM)") (class "Default")
      (node (ref "R11") (pin "2") (pinfunction "2_2") (pintype "passive"))
      (node (ref "U$4") (pin "4") (pinfunction "ILIM_4") (pintype "bidirectional"))
    )
    (net (code "55") (name "Net-(U$6A-B)") (class "Default")
      (node (ref "RB1") (pin "1") (pinfunction "1_1") (pintype "passive"))
      (node (ref "U$6") (pin "5") (pinfunction "B_5") (pintype "passive"))
    )
    (net (code "56") (name "RED") (class "Default")
      (node (ref "RR") (pin "5") (pinfunction "2_5") (pintype "passive"))
      (node (ref "RR") (pin "6") (pinfunction "2_6") (pintype "passive"))
      (node (ref "RR") (pin "7") (pinfunction "2_7") (pintype "passive"))
      (node (ref "RR") (pin "8") (pinfunction "2_8") (pintype "passive"))
      (node (ref "U$6") (pin "3") (pinfunction "C_3") (pintype "passive"))
    )
    (net (code "57") (name "RST_ESP") (class "Default")
      (node (ref "RPU") (pin "7") (pinfunction "2_7") (pintype "passive"))
      (node (ref "SW_RST") (pin "P$1") (pinfunction "1_P$1") (pintype "passive"))
      (node (ref "U$3") (pin "3") (pinfunction "C_3") (pintype "passive"))
      (node (ref "X1") (pin "1") (pinfunction "RESET_1") (pintype "input"))
    )
    (net (code "58") (name "RTS") (class "Default")
      (node (ref "CH340G") (pin "14") (pinfunction "RTS_14") (pintype "bidirectional"))
      (node (ref "R4") (pin "1") (pinfunction "1_1") (pintype "passive"))
      (node (ref "U$3") (pin "4") (pinfunction "E_4") (pintype "passive"))
    )
    (net (code "59") (name "RX_ESP") (class "Default")
      (node (ref "R3") (pin "1") (pinfunction "1_1") (pintype "passive"))
      (node (ref "X1") (pin "15") (pinfunction "RXD_15") (pintype "input"))
    )
    (net (code "60") (name "SCL") (class "Default")
      (node (ref "IC1") (pin "14") (pinfunction "SCL_14") (pintype "input"))
      (node (ref "JP2") (pin "P$3") (pinfunction "3_P$3") (pintype "passive"))
      (node (ref "R13") (pin "2") (pinfunction "2_2") (pintype "passive"))
      (node (ref "U$10") (pin "P$4") (pinfunction "SCL_P$4") (pintype "bidirectional"))
      (node (ref "U$2") (pin "7") (pinfunction "PB2(SCK/ADC1)_7") (pintype "bidirectional"))
      (node (ref "X1") (pin "14") (pinfunction "GPIO4_14") (pintype "bidirectional"))
    )
    (net (code "61") (name "SD_CS") (class "Default")
      (node (ref "U1") (pin "P$2") (pinfunction "CS_P$2") (pintype "bidirectional"))
      (node (ref "X1") (pin "4") (pinfunction "GPIO16_4") (pintype "bidirectional"))
    )
    (net (code "62") (name "SD_IN") (class "Default")
      (node (ref "IC1") (pin "5") (pinfunction "P1_5") (pintype "bidirectional"))
      (node (ref "U1") (pin "SW1") (pinfunction "CD1_SW1") (pintype "bidirectional"))
    )
    (net (code "63") (name "SPKR") (class "Default")
      (node (ref "TP1") (pin "TP") (pinfunction "TP_TP") (pintype "input"))
      (node (ref "X1") (pin "13") (pinfunction "GPIO5_13") (pintype "bidirectional"))
    )
    (net (code "64") (name "TX_ESP") (class "Default")
      (node (ref "R2") (pin "1") (pinfunction "1_1") (pintype "passive"))
      (node (ref "X1") (pin "16") (pinfunction "TXD_16") (pintype "output"))
    )
    (net (code "65") (name "VBAT") (class "Default")
      (node (ref "C8") (pin "1") (pinfunction "1_1") (pintype "passive"))
      (node (ref "IC3") (pin "3") (pinfunction "VBAT_3") (pintype "bidirectional"))
      (node (ref "J1") (pin "2") (pinfunction "+_2") (pintype "bidirectional"))
      (node (ref "R6") (pin "2") (pinfunction "2_2") (pintype "passive"))
      (node (ref "U$4") (pin "6") (pinfunction "IN2_6") (pintype "bidirectional"))
    )
    (net (code "66") (name "VBUS") (class "Default")
      (node (ref "C7") (pin "2") (pinfunction "2_2") (pintype "passive"))
      (node (ref "CHARGE") (pin "A") (pinfunction "A_A") (pintype "passive"))
      (node (ref "F1") (pin "2") (pinfunction "2_2") (pintype "bidirectional"))
      (node (ref "IC3") (pin "4") (pinfunction "VDD_4") (pintype "power_in"))
      (node (ref "U$4") (pin "8") (pinfunction "IN1_8") (pintype "bidirectional"))
    )
    (net (code "67") (name "VCC") (class "Default")
      (node (ref "C10") (pin "2") (pinfunction "2_2") (pintype "passive"))
      (node (ref "C11") (pin "2") (pinfunction "2_2") (pintype "passive"))
      (node (ref "C3") (pin "1") (pinfunction "1_1") (pintype "passive"))
      (node (ref "C4") (pin "1") (pinfunction "1_1") (pintype "passive"))
      (node (ref "C9") (pin "2") (pinfunction "2_2") (pintype "passive"))
      (node (ref "CH340G") (pin "16") (pinfunction "VCC_16") (pintype "bidirectional"))
      (node (ref "CH340G") (pin "4") (pinfunction "V3_4") (pintype "bidirectional"))
      (node (ref "D1") (pin "C") (pinfunction "-_C") (pintype "passive"))
      (node (ref "IC1") (pin "16") (pinfunction "VDD_16") (pintype "power_in"))
      (node (ref "JP2") (pin "P$2") (pinfunction "2_P$2") (pintype "passive"))
      (node (ref "LED1") (pin "4") (pinfunction "A_4") (pintype "passive"))
      (node (ref "LED2") (pin "4") (pinfunction "A_4") (pintype "passive"))
      (node (ref "LED3") (pin "4") (pinfunction "A_4") (pintype "passive"))
      (node (ref "LED4") (pin "4") (pinfunction "A_4") (pintype "passive"))
      (node (ref "R1") (pin "2") (pinfunction "2_2") (pintype "passive"))
      (node (ref "R13") (pin "1") (pinfunction "1_1") (pintype "passive"))
      (node (ref "R15") (pin "1") (pinfunction "1_1") (pintype "passive"))
      (node (ref "RPU") (pin "1") (pinfunction "1_1") (pintype "passive"))
      (node (ref "RPU") (pin "2") (pinfunction "1_2") (pintype "passive"))
      (node (ref "RPU") (pin "3") (pinfunction "1_3") (pintype "passive"))
      (node (ref "RPU") (pin "4") (pinfunction "1_4") (pintype "passive"))
      (node (ref "U$1") (pin "1") (pinfunction "VDD_1") (pintype "power_in"))
      (node (ref "U$1") (pin "6") (pinfunction "OSC_6") (pintype "passive"))
      (node (ref "U$10") (pin "P$2") (pinfunction "VCC_P$2") (pintype "bidirectional"))
      (node (ref "U$2") (pin "8") (pinfunction "VCC_8") (pintype "bidirectional"))
      (node (ref "U$9") (pin "P$5") (pinfunction "VOUT_P$5") (pintype "bidirectional"))
      (node (ref "U1") (pin "P$4") (pinfunction "VCC_P$4") (pintype "bidirectional"))
      (node (ref "X1") (pin "8") (pinfunction "VCC_8") (pintype "power_in"))
    )
    (net (code "68") (name "VREG_IN") (class "Default")
      (node (ref "C2") (pin "1") (pinfunction "1_1") (pintype "passive"))
      (node (ref "S2") (pin "1") (pinfunction "O_1") (pintype "passive"))
      (node (ref "U$4") (pin "7") (pinfunction "OUT_7") (pintype "bidirectional"))
      (node (ref "U$9") (pin "P$1") (pinfunction "VIN_P$1") (pintype "bidirectional"))
    )
    (net (code "69") (name "unconnected-(CH340G-CTS-Pad9)") (class "Default")
      (node (ref "CH340G") (pin "9") (pinfunction "CTS_9") (pintype "bidirectional"))
    )
    (net (code "70") (name "unconnected-(CH340G-DCD-Pad12)") (class "Default")
      (node (ref "CH340G") (pin "12") (pinfunction "DCD_12") (pintype "bidirectional"))
    )
    (net (code "71") (name "unconnected-(CH340G-DSR-Pad10)") (class "Default")
      (node (ref "CH340G") (pin "10") (pinfunction "DSR_10") (pintype "bidirectional"))
    )
    (net (code "72") (name "unconnected-(CH340G-RI-Pad11)") (class "Default")
      (node (ref "CH340G") (pin "11") (pinfunction "RI_11") (pintype "bidirectional"))
    )
    (net (code "73") (name "unconnected-(CH340G-RS232-Pad15)") (class "Default")
      (node (ref "CH340G") (pin "15") (pinfunction "RS232_15") (pintype "bidirectional"))
    )
    (net (code "74") (name "unconnected-(IC1-~{INT}-Pad13)") (class "Default")
      (node (ref "IC1") (pin "13") (pinfunction "~{INT}_13") (pintype "output"))
    )
    (net (code "75") (name "unconnected-(J1-PAD1-PadNC1)") (class "Default")
      (node (ref "J1") (pin "NC1") (pinfunction "PAD1_NC1") (pintype "bidirectional"))
    )
    (net (code "76") (name "unconnected-(J1-PAD2-PadNC2)") (class "Default")
      (node (ref "J1") (pin "NC2") (pinfunction "PAD2_NC2") (pintype "bidirectional"))
    )
    (net (code "77") (name "unconnected-(JP1-ID-PadID1)") (class "Default")
      (node (ref "JP1") (pin "ID1") (pinfunction "ID_ID1") (pintype "bidirectional"))
    )
    (net (code "78") (name "unconnected-(U$4-STAT-Pad1)") (class "Default")
      (node (ref "U$4") (pin "1") (pinfunction "STAT_1") (pintype "bidirectional"))
    )
    (net (code "79") (name "unconnected-(U1-NC-PadP$1)") (class "Default")
      (node (ref "U1") (pin "P$1") (pinfunction "NC_P$1") (pintype "bidirectional"))
    )
    (net (code "80") (name "unconnected-(U1-RSV-PadP$8)") (class "Default")
      (node (ref "U1") (pin "P$8") (pinfunction "RSV_P$8") (pintype "bidirectional"))
    )
  )
)
